# 0117-FETz4.net
KiCad netlist of a schematic drawn in EAGLE
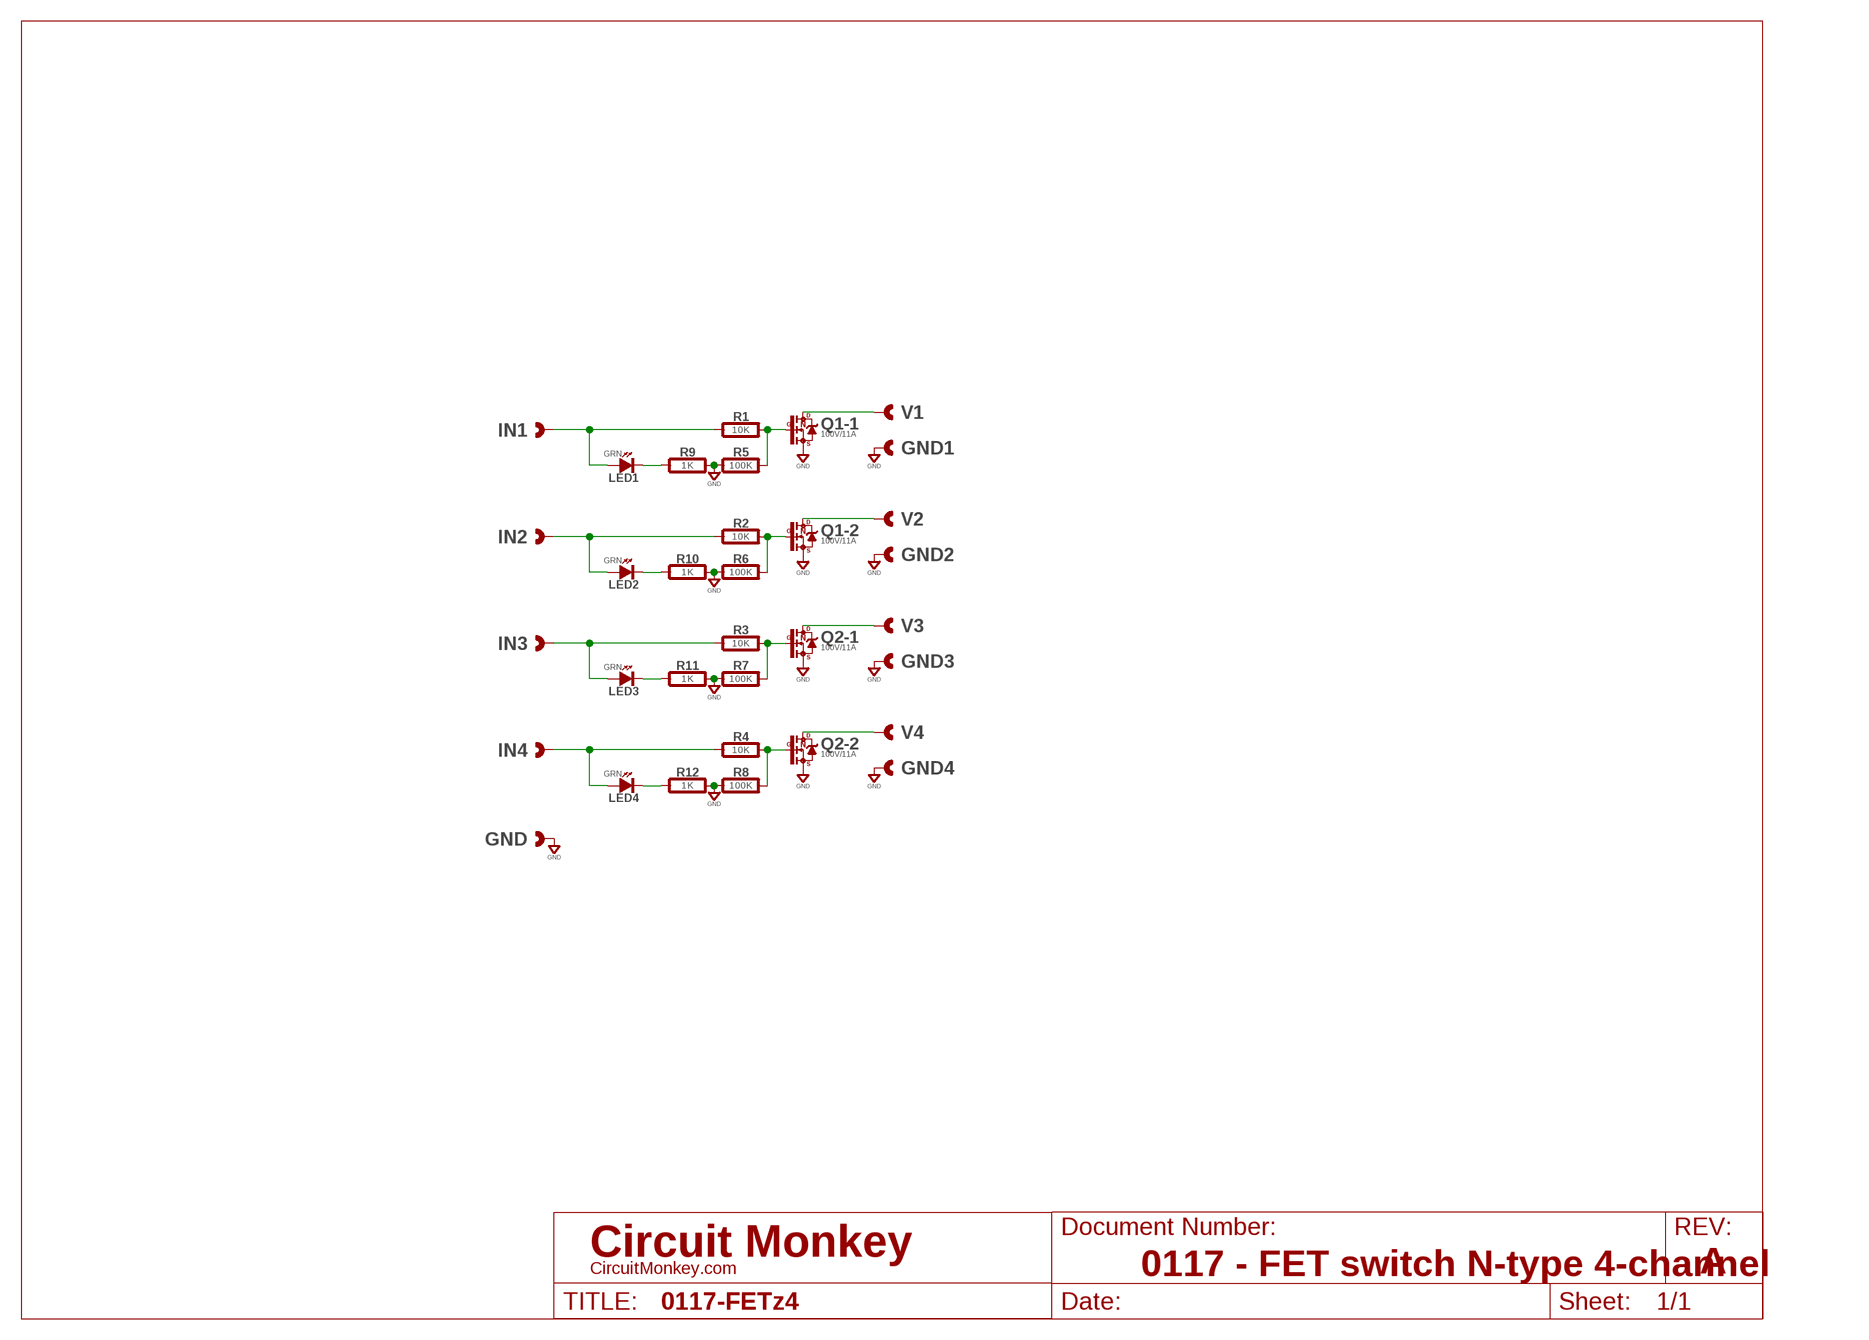
[diagram p0: schematic, sheet 1]

(export (version "E")
  (design (tool "Eeschema 10.0.6"))
  (components
    (comp (ref "GND")
      (value "CAST-01X12.00MM")
      (footprint "eagle-import:CAST01-2.00MM")
      (libsource (lib "eagle-import") (part "CAST-01X12.00MM"))
    )
    (comp (ref "GND1")
      (value "CAST-01X12.00MM")
      (footprint "eagle-import:CAST01-2.00MM")
      (libsource (lib "eagle-import") (part "CAST-01X12.00MM"))
    )
    (comp (ref "GND2")
      (value "CAST-01X12.00MM")
      (footprint "eagle-import:CAST01-2.00MM")
      (libsource (lib "eagle-import") (part "CAST-01X12.00MM"))
    )
    (comp (ref "GND3")
      (value "CAST-01X12.00MM")
      (footprint "eagle-import:CAST01-2.00MM")
      (libsource (lib "eagle-import") (part "CAST-01X12.00MM"))
    )
    (comp (ref "GND4")
      (value "CAST-01X12.00MM")
      (footprint "eagle-import:CAST01-2.00MM")
      (libsource (lib "eagle-import") (part "CAST-01X12.00MM"))
    )
    (comp (ref "IN1")
      (value "CAST-01X12.00MM")
      (footprint "eagle-import:CAST01-2.00MM")
      (libsource (lib "eagle-import") (part "CAST-01X12.00MM"))
    )
    (comp (ref "IN2")
      (value "CAST-01X12.00MM")
      (footprint "eagle-import:CAST01-2.00MM")
      (libsource (lib "eagle-import") (part "CAST-01X12.00MM"))
    )
    (comp (ref "IN3")
      (value "CAST-01X12.00MM")
      (footprint "eagle-import:CAST01-2.00MM")
      (libsource (lib "eagle-import") (part "CAST-01X12.00MM"))
    )
    (comp (ref "IN4")
      (value "CAST-01X12.00MM")
      (footprint "eagle-import:CAST01-2.00MM")
      (libsource (lib "eagle-import") (part "CAST-01X12.00MM"))
    )
    (comp (ref "LED1")
      (value "GRN")
      (footprint "eagle-import:SMD_0603")
      (libsource (lib "eagle-import") (part "SMT0603"))
    )
    (comp (ref "LED2")
      (value "GRN")
      (footprint "eagle-import:SMD_0603")
      (libsource (lib "eagle-import") (part "SMT0603"))
    )
    (comp (ref "LED3")
      (value "GRN")
      (footprint "eagle-import:SMD_0603")
      (libsource (lib "eagle-import") (part "SMT0603"))
    )
    (comp (ref "LED4")
      (value "GRN")
      (footprint "eagle-import:SMD_0603")
      (libsource (lib "eagle-import") (part "SMT0603"))
    )
    (comp (ref "Q1")
      (value "100V/11A")
      (footprint "eagle-import:POWER_PAK-SO-8L-DUAL")
      (fields (field (name "MFR") "Vishay") (field (name "MPN") "SQJB68EP"))
      (libsource (lib "eagle-import") (part "N-FET_DUALSQJB68EP"))
    )
    (comp (ref "Q2")
      (value "100V/11A")
      (footprint "eagle-import:POWER_PAK-SO-8L-DUAL")
      (fields (field (name "MFR") "Vishay") (field (name "MPN") "SQJB68EP"))
      (libsource (lib "eagle-import") (part "N-FET_DUALSQJB68EP"))
    )
    (comp (ref "R1")
      (value "10K")
      (footprint "eagle-import:0603-RES")
      (libsource (lib "eagle-import") (part "RESISTOR0603"))
    )
    (comp (ref "R2")
      (value "10K")
      (footprint "eagle-import:0603-RES")
      (libsource (lib "eagle-import") (part "RESISTOR0603"))
    )
    (comp (ref "R3")
      (value "10K")
      (footprint "eagle-import:0603-RES")
      (libsource (lib "eagle-import") (part "RESISTOR0603"))
    )
    (comp (ref "R4")
      (value "10K")
      (footprint "eagle-import:0603-RES")
      (libsource (lib "eagle-import") (part "RESISTOR0603"))
    )
    (comp (ref "R5")
      (value "100K")
      (footprint "eagle-import:0603-RES")
      (libsource (lib "eagle-import") (part "RESISTOR0603"))
    )
    (comp (ref "R6")
      (value "100K")
      (footprint "eagle-import:0603-RES")
      (libsource (lib "eagle-import") (part "RESISTOR0603"))
    )
    (comp (ref "R7")
      (value "100K")
      (footprint "eagle-import:0603-RES")
      (libsource (lib "eagle-import") (part "RESISTOR0603"))
    )
    (comp (ref "R8")
      (value "100K")
      (footprint "eagle-import:0603-RES")
      (libsource (lib "eagle-import") (part "RESISTOR0603"))
    )
    (comp (ref "R9")
      (value "1K")
      (footprint "eagle-import:0603-RES")
      (libsource (lib "eagle-import") (part "RESISTOR0603"))
    )
    (comp (ref "R10")
      (value "1K")
      (footprint "eagle-import:0603-RES")
      (libsource (lib "eagle-import") (part "RESISTOR0603"))
    )
    (comp (ref "R11")
      (value "1K")
      (footprint "eagle-import:0603-RES")
      (libsource (lib "eagle-import") (part "RESISTOR0603"))
    )
    (comp (ref "R12")
      (value "1K")
      (footprint "eagle-import:0603-RES")
      (libsource (lib "eagle-import") (part "RESISTOR0603"))
    )
    (comp (ref "V1")
      (value "CAST-01X12.00MM")
      (footprint "eagle-import:CAST01-2.00MM")
      (libsource (lib "eagle-import") (part "CAST-01X12.00MM"))
    )
    (comp (ref "V2")
      (value "CAST-01X12.00MM")
      (footprint "eagle-import:CAST01-2.00MM")
      (libsource (lib "eagle-import") (part "CAST-01X12.00MM"))
    )
    (comp (ref "V3")
      (value "CAST-01X12.00MM")
      (footprint "eagle-import:CAST01-2.00MM")
      (libsource (lib "eagle-import") (part "CAST-01X12.00MM"))
    )
    (comp (ref "V4")
      (value "CAST-01X12.00MM")
      (footprint "eagle-import:CAST01-2.00MM")
      (libsource (lib "eagle-import") (part "CAST-01X12.00MM"))
    )
  )
  (nets
    (net (code "1") (name "GND") (class "Default")
      (node (ref "GND") (pin "1") (pinfunction "1_1") (pintype "bidirectional"))
      (node (ref "GND") (pin "P$1") (pinfunction "1_P$1") (pintype "bidirectional"))
      (node (ref "GND") (pin "P$2") (pinfunction "1_P$2") (pintype "bidirectional"))
      (node (ref "GND1") (pin "1") (pinfunction "1_1") (pintype "bidirectional"))
      (node (ref "GND1") (pin "P$1") (pinfunction "1_P$1") (pintype "bidirectional"))
      (node (ref "GND1") (pin "P$2") (pinfunction "1_P$2") (pintype "bidirectional"))
      (node (ref "GND2") (pin "1") (pinfunction "1_1") (pintype "bidirectional"))
      (node (ref "GND2") (pin "P$1") (pinfunction "1_P$1") (pintype "bidirectional"))
      (node (ref "GND2") (pin "P$2") (pinfunction "1_P$2") (pintype "bidirectional"))
      (node (ref "GND3") (pin "1") (pinfunction "1_1") (pintype "bidirectional"))
      (node (ref "GND3") (pin "P$1") (pinfunction "1_P$1") (pintype "bidirectional"))
      (node (ref "GND3") (pin "P$2") (pinfunction "1_P$2") (pintype "bidirectional"))
      (node (ref "GND4") (pin "1") (pinfunction "1_1") (pintype "bidirectional"))
      (node (ref "GND4") (pin "P$1") (pinfunction "1_P$1") (pintype "bidirectional"))
      (node (ref "GND4") (pin "P$2") (pinfunction "1_P$2") (pintype "bidirectional"))
      (node (ref "Q1") (pin "S1") (pinfunction "S_S1") (pintype "bidirectional"))
      (node (ref "Q1") (pin "S2") (pinfunction "S_S2") (pintype "bidirectional"))
      (node (ref "Q2") (pin "S1") (pinfunction "S_S1") (pintype "bidirectional"))
      (node (ref "Q2") (pin "S2") (pinfunction "S_S2") (pintype "bidirectional"))
      (node (ref "R10") (pin "2") (pinfunction "2_2") (pintype "passive"))
      (node (ref "R11") (pin "2") (pinfunction "2_2") (pintype "passive"))
      (node (ref "R12") (pin "2") (pinfunction "2_2") (pintype "passive"))
      (node (ref "R5") (pin "1") (pinfunction "1_1") (pintype "passive"))
      (node (ref "R6") (pin "1") (pinfunction "1_1") (pintype "passive"))
      (node (ref "R7") (pin "1") (pinfunction "1_1") (pintype "passive"))
      (node (ref "R8") (pin "1") (pinfunction "1_1") (pintype "passive"))
      (node (ref "R9") (pin "2") (pinfunction "2_2") (pintype "passive"))
    )
    (net (code "2") (name "Net-(IN1-1-PadP$1)") (class "Default")
      (node (ref "IN1") (pin "1") (pinfunction "1_1") (pintype "bidirectional"))
      (node (ref "IN1") (pin "P$1") (pinfunction "1_P$1") (pintype "bidirectional"))
      (node (ref "IN1") (pin "P$2") (pinfunction "1_P$2") (pintype "bidirectional"))
      (node (ref "LED1") (pin "A") (pinfunction "A_A") (pintype "passive"))
      (node (ref "R1") (pin "1") (pinfunction "1_1") (pintype "passive"))
    )
    (net (code "3") (name "Net-(IN2-1-PadP$1)") (class "Default")
      (node (ref "IN2") (pin "1") (pinfunction "1_1") (pintype "bidirectional"))
      (node (ref "IN2") (pin "P$1") (pinfunction "1_P$1") (pintype "bidirectional"))
      (node (ref "IN2") (pin "P$2") (pinfunction "1_P$2") (pintype "bidirectional"))
      (node (ref "LED2") (pin "A") (pinfunction "A_A") (pintype "passive"))
      (node (ref "R2") (pin "1") (pinfunction "1_1") (pintype "passive"))
    )
    (net (code "4") (name "Net-(IN3-1-PadP$1)") (class "Default")
      (node (ref "IN3") (pin "1") (pinfunction "1_1") (pintype "bidirectional"))
      (node (ref "IN3") (pin "P$1") (pinfunction "1_P$1") (pintype "bidirectional"))
      (node (ref "IN3") (pin "P$2") (pinfunction "1_P$2") (pintype "bidirectional"))
      (node (ref "LED3") (pin "A") (pinfunction "A_A") (pintype "passive"))
      (node (ref "R3") (pin "1") (pinfunction "1_1") (pintype "passive"))
    )
    (net (code "5") (name "Net-(IN4-1-PadP$1)") (class "Default")
      (node (ref "IN4") (pin "1") (pinfunction "1_1") (pintype "bidirectional"))
      (node (ref "IN4") (pin "P$1") (pinfunction "1_P$1") (pintype "bidirectional"))
      (node (ref "IN4") (pin "P$2") (pinfunction "1_P$2") (pintype "bidirectional"))
      (node (ref "LED4") (pin "A") (pinfunction "A_A") (pintype "passive"))
      (node (ref "R4") (pin "1") (pinfunction "1_1") (pintype "passive"))
    )
    (net (code "6") (name "Net-(LED1-C)") (class "Default")
      (node (ref "LED1") (pin "K") (pinfunction "C_K") (pintype "passive"))
      (node (ref "R9") (pin "1") (pinfunction "1_1") (pintype "passive"))
    )
    (net (code "7") (name "Net-(LED2-C)") (class "Default")
      (node (ref "LED2") (pin "K") (pinfunction "C_K") (pintype "passive"))
      (node (ref "R10") (pin "1") (pinfunction "1_1") (pintype "passive"))
    )
    (net (code "8") (name "Net-(LED3-C)") (class "Default")
      (node (ref "LED3") (pin "K") (pinfunction "C_K") (pintype "passive"))
      (node (ref "R11") (pin "1") (pinfunction "1_1") (pintype "passive"))
    )
    (net (code "9") (name "Net-(LED4-C)") (class "Default")
      (node (ref "LED4") (pin "K") (pinfunction "C_K") (pintype "passive"))
      (node (ref "R12") (pin "1") (pinfunction "1_1") (pintype "passive"))
    )
    (net (code "10") (name "Net-(Q1A-D-PadD1)") (class "Default")
      (node (ref "Q1") (pin "D1") (pinfunction "D_D1") (pintype "bidirectional"))
      (node (ref "Q1") (pin "D1B") (pinfunction "D_D1B") (pintype "bidirectional"))
      (node (ref "Q1") (pin "D1C") (pinfunction "D_D1C") (pintype "bidirectional"))
      (node (ref "V1") (pin "1") (pinfunction "1_1") (pintype "bidirectional"))
      (node (ref "V1") (pin "P$1") (pinfunction "1_P$1") (pintype "bidirectional"))
      (node (ref "V1") (pin "P$2") (pinfunction "1_P$2") (pintype "bidirectional"))
    )
    (net (code "11") (name "Net-(Q1A-G)") (class "Default")
      (node (ref "Q1") (pin "G1") (pinfunction "G_G1") (pintype "bidirectional"))
      (node (ref "R1") (pin "2") (pinfunction "2_2") (pintype "passive"))
      (node (ref "R5") (pin "2") (pinfunction "2_2") (pintype "passive"))
    )
    (net (code "12") (name "Net-(Q1B-D-PadD2)") (class "Default")
      (node (ref "Q1") (pin "D2") (pinfunction "D_D2") (pintype "bidirectional"))
      (node (ref "Q1") (pin "D2B") (pinfunction "D_D2B") (pintype "bidirectional"))
      (node (ref "Q1") (pin "D2C") (pinfunction "D_D2C") (pintype "bidirectional"))
      (node (ref "V2") (pin "1") (pinfunction "1_1") (pintype "bidirectional"))
      (node (ref "V2") (pin "P$1") (pinfunction "1_P$1") (pintype "bidirectional"))
      (node (ref "V2") (pin "P$2") (pinfunction "1_P$2") (pintype "bidirectional"))
    )
    (net (code "13") (name "Net-(Q1B-G)") (class "Default")
      (node (ref "Q1") (pin "G2") (pinfunction "G_G2") (pintype "bidirectional"))
      (node (ref "R2") (pin "2") (pinfunction "2_2") (pintype "passive"))
      (node (ref "R6") (pin "2") (pinfunction "2_2") (pintype "passive"))
    )
    (net (code "14") (name "Net-(Q2A-D-PadD1)") (class "Default")
      (node (ref "Q2") (pin "D1") (pinfunction "D_D1") (pintype "bidirectional"))
      (node (ref "Q2") (pin "D1B") (pinfunction "D_D1B") (pintype "bidirectional"))
      (node (ref "Q2") (pin "D1C") (pinfunction "D_D1C") (pintype "bidirectional"))
      (node (ref "V3") (pin "1") (pinfunction "1_1") (pintype "bidirectional"))
      (node (ref "V3") (pin "P$1") (pinfunction "1_P$1") (pintype "bidirectional"))
      (node (ref "V3") (pin "P$2") (pinfunction "1_P$2") (pintype "bidirectional"))
    )
    (net (code "15") (name "Net-(Q2A-G)") (class "Default")
      (node (ref "Q2") (pin "G1") (pinfunction "G_G1") (pintype "bidirectional"))
      (node (ref "R3") (pin "2") (pinfunction "2_2") (pintype "passive"))
      (node (ref "R7") (pin "2") (pinfunction "2_2") (pintype "passive"))
    )
    (net (code "16") (name "Net-(Q2B-D-PadD2)") (class "Default")
      (node (ref "Q2") (pin "D2") (pinfunction "D_D2") (pintype "bidirectional"))
      (node (ref "Q2") (pin "D2B") (pinfunction "D_D2B") (pintype "bidirectional"))
      (node (ref "Q2") (pin "D2C") (pinfunction "D_D2C") (pintype "bidirectional"))
      (node (ref "V4") (pin "1") (pinfunction "1_1") (pintype "bidirectional"))
      (node (ref "V4") (pin "P$1") (pinfunction "1_P$1") (pintype "bidirectional"))
      (node (ref "V4") (pin "P$2") (pinfunction "1_P$2") (pintype "bidirectional"))
    )
    (net (code "17") (name "Net-(Q2B-G)") (class "Default")
      (node (ref "Q2") (pin "G2") (pinfunction "G_G2") (pintype "bidirectional"))
      (node (ref "R4") (pin "2") (pinfunction "2_2") (pintype "passive"))
      (node (ref "R8") (pin "2") (pinfunction "2_2") (pintype "passive"))
    )
  )
)
